# Power_Distribution_-_Load_Switchs_and_Co.net
KiCad netlist of a schematic drawn in Altium Designer
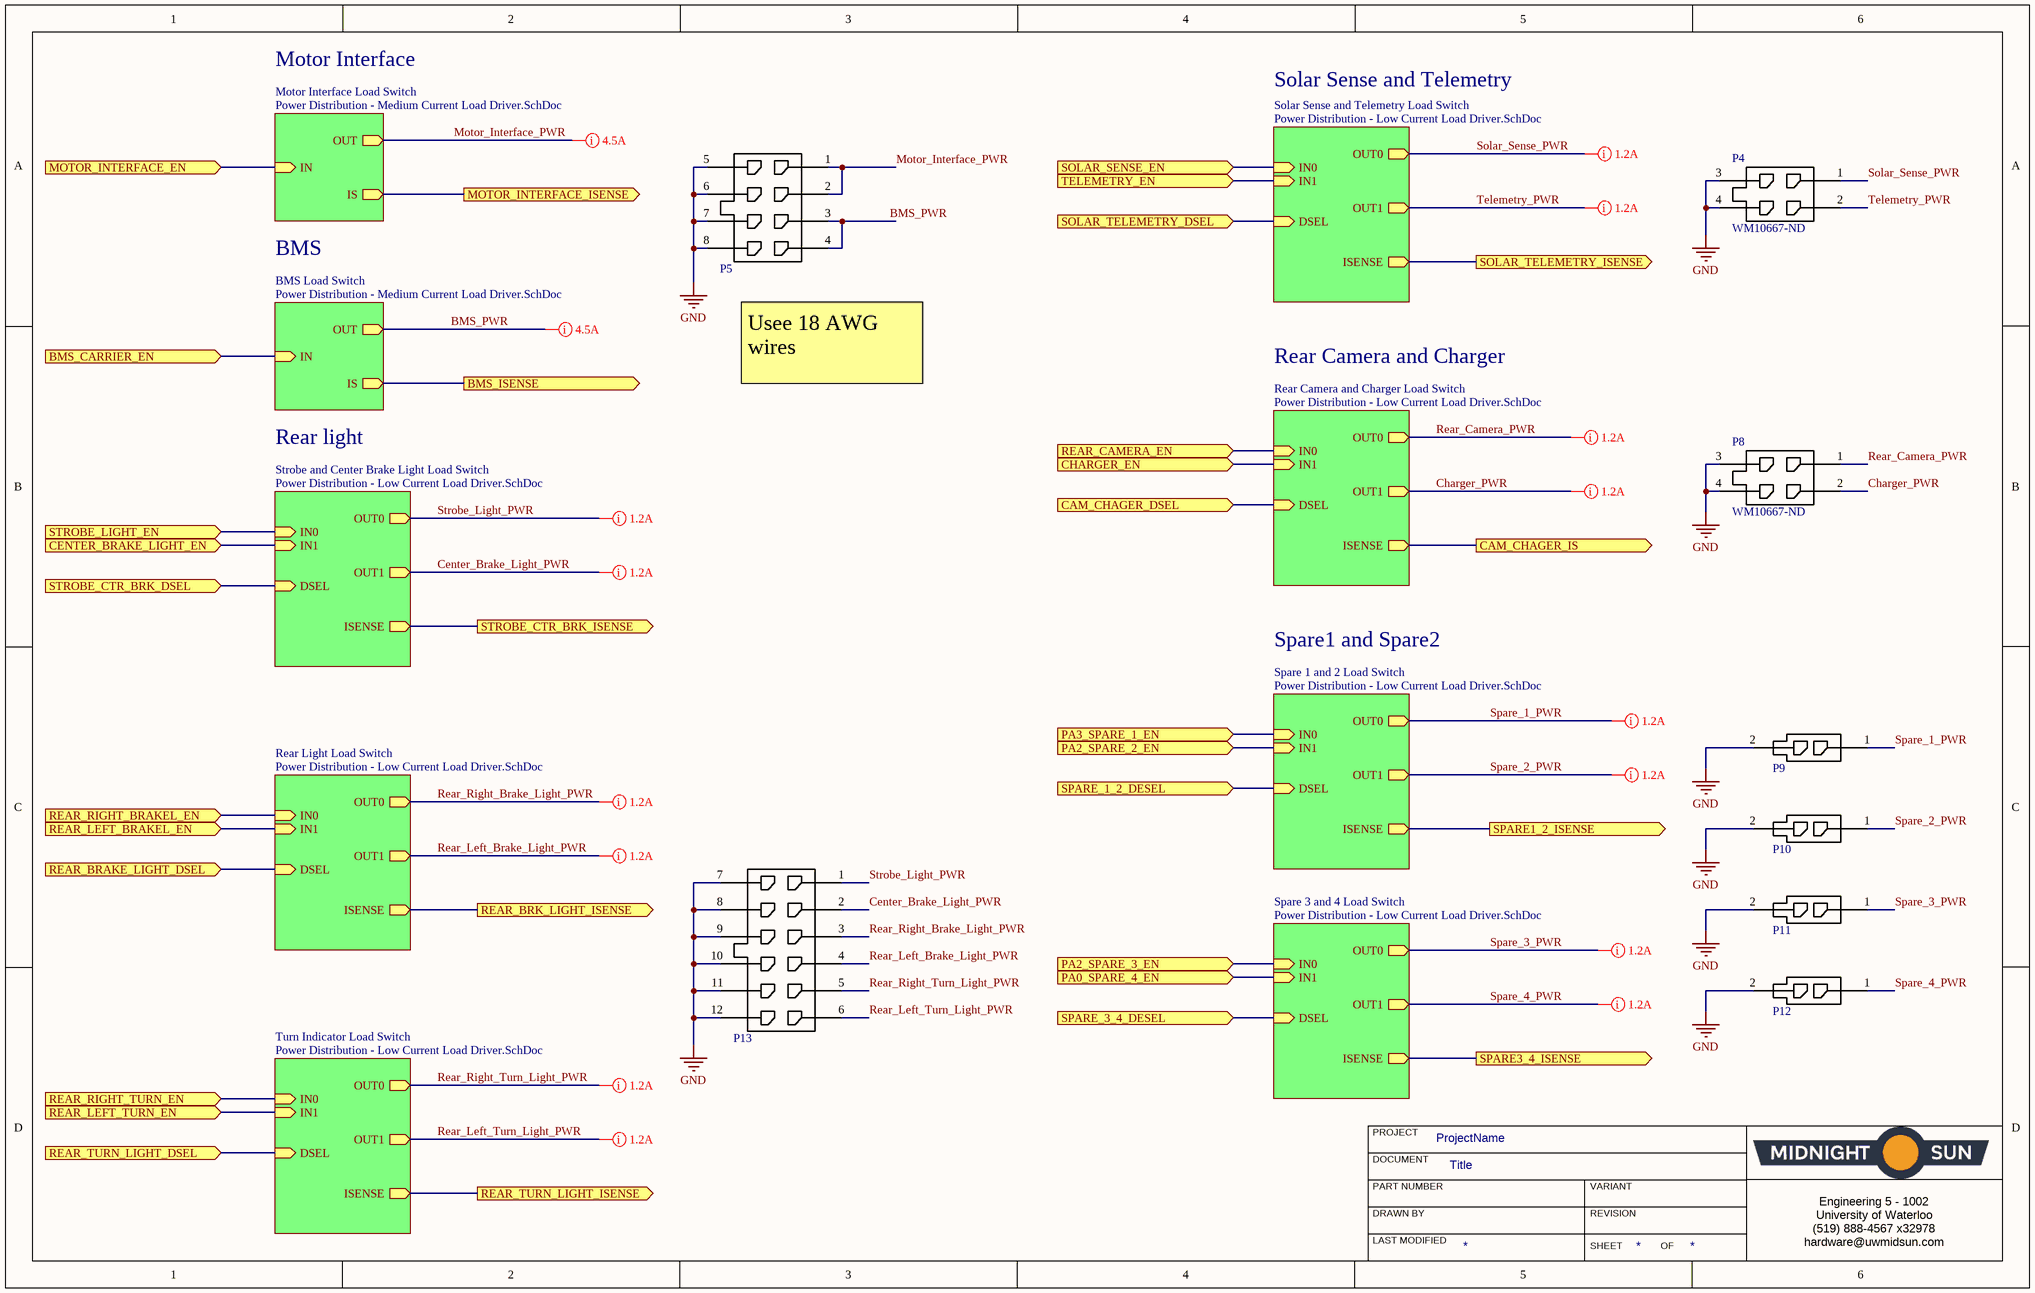
[diagram p0: Power Distribution - Load Switchs and Connectos.SchDoc]

(export (version "E")
  (design (tool "Eeschema 10.0.6"))
  (components
    (comp (ref "P4")
      (value "CONN 4POS MICRO-FIT 3mm")
      (footprint "CONN 4POS MICROFIT (2x2)")
      (fields
        (field (name "MANUFACTURER") "Molex, LLC")
        (field (name "MANUFACTURER PART NUMBER") "430450427")
        (field (name "SUPPLIER PART NUMBER 1") "WM10667-ND")
      )
      (libsource (lib "Schematic Diagrams") (part "CONN 4POS MICRO-FIT 3mm"))
    )
    (comp (ref "P5")
      (value "CONN 8POS MICRO-FIT 3mm")
      (footprint "CONN, 8POS MICRO-FIT")
      (description "Connector Header Through Hole 6 position 0.118\" (3.00mm)")
      (fields
        (field (name "MANUFACTURER") "Molex, LLC")
        (field (name "MANUFACTURER PART NUMBER") "0430450827")
      )
      (libsource (lib "Schematic Diagrams") (part "CONN 8POS MICRO-FIT 3mm"))
    )
    (comp (ref "P8")
      (value "CONN 4POS MICRO-FIT 3mm")
      (footprint "CONN 4POS MICROFIT (2x2)")
      (fields
        (field (name "MANUFACTURER") "Molex, LLC")
        (field (name "MANUFACTURER PART NUMBER") "430450427")
        (field (name "SUPPLIER PART NUMBER 1") "WM10667-ND")
      )
      (libsource (lib "Schematic Diagrams") (part "CONN 4POS MICRO-FIT 3mm"))
    )
    (comp (ref "P9")
      (value "CONN 2POS MICRO-FIT 3mm")
      (footprint "CONN, 2POS MICRO-FIT")
      (description "Connector Header Through Hole 2 position")
      (fields (field (name "MANUFACTURER") "Molex") (field (name "MANUFACTURER PART NUMBER") "43045-0227"))
      (libsource (lib "Schematic Diagrams") (part "CONN 2POS MICRO-FIT 3mm"))
    )
    (comp (ref "P10")
      (value "CONN 2POS MICRO-FIT 3mm")
      (footprint "CONN, 2POS MICRO-FIT")
      (description "Connector Header Through Hole 2 position")
      (fields (field (name "MANUFACTURER") "Molex") (field (name "MANUFACTURER PART NUMBER") "43045-0227"))
      (libsource (lib "Schematic Diagrams") (part "CONN 2POS MICRO-FIT 3mm"))
    )
    (comp (ref "P11")
      (value "CONN 2POS MICRO-FIT 3mm")
      (footprint "CONN, 2POS MICRO-FIT")
      (description "Connector Header Through Hole 2 position")
      (fields (field (name "MANUFACTURER") "Molex") (field (name "MANUFACTURER PART NUMBER") "43045-0227"))
      (libsource (lib "Schematic Diagrams") (part "CONN 2POS MICRO-FIT 3mm"))
    )
    (comp (ref "P12")
      (value "CONN 2POS MICRO-FIT 3mm")
      (footprint "CONN, 2POS MICRO-FIT")
      (description "Connector Header Through Hole 2 position")
      (fields (field (name "MANUFACTURER") "Molex") (field (name "MANUFACTURER PART NUMBER") "43045-0227"))
      (libsource (lib "Schematic Diagrams") (part "CONN 2POS MICRO-FIT 3mm"))
    )
    (comp (ref "P13")
      (value "CONN 12POS MICRO-FIT 3mm")
      (footprint "CONN, 12POS MICRO-FIT 3mm")
      (description "Connector Header Through Hole 12 position 0.118\" (3.00mm)")
      (fields
        (field (name "MANUFACTURER") "Molex, LLC")
        (field (name "MANUFACTURER PART NUMBER") "0430451227")
      )
      (libsource (lib "Schematic Diagrams") (part "CONN 12POS MICRO-FIT 3mm"))
    )
  )
  (nets
    (net (code "3") (name "/BMS_PWR") (class "Default")
      (node (ref "P5") (pin "3") (pinfunction "3_3") (pintype "passive"))
      (node (ref "P5") (pin "4") (pinfunction "4_4") (pintype "passive"))
    )
    (net (code "8") (name "/Center_Brake_Light_PWR") (class "Default")
      (node (ref "P13") (pin "2") (pinfunction "2_2") (pintype "passive"))
    )
    (net (code "9") (name "/Charger_PWR") (class "Default")
      (node (ref "P8") (pin "2") (pinfunction "2_2") (pintype "passive"))
    )
    (net (code "12") (name "/Motor_Interface_PWR") (class "Default")
      (node (ref "P5") (pin "1") (pinfunction "1_1") (pintype "passive"))
      (node (ref "P5") (pin "2") (pinfunction "2_2") (pintype "passive"))
    )
    (net (code "26") (name "/Rear_Camera_PWR") (class "Default")
      (node (ref "P8") (pin "1") (pinfunction "1_1") (pintype "passive"))
    )
    (net (code "27") (name "/Rear_Left_Brake_Light_PWR") (class "Default")
      (node (ref "P13") (pin "4") (pinfunction "4_4") (pintype "passive"))
    )
    (net (code "28") (name "/Rear_Left_Turn_Light_PWR") (class "Default")
      (node (ref "P13") (pin "6") (pinfunction "6_6") (pintype "passive"))
    )
    (net (code "29") (name "/Rear_Right_Brake_Light_PWR") (class "Default")
      (node (ref "P13") (pin "3") (pinfunction "3_3") (pintype "passive"))
    )
    (net (code "30") (name "/Rear_Right_Turn_Light_PWR") (class "Default")
      (node (ref "P13") (pin "5") (pinfunction "5_5") (pintype "passive"))
    )
    (net (code "41") (name "/Solar_Sense_PWR") (class "Default")
      (node (ref "P4") (pin "1") (pinfunction "1_1") (pintype "passive"))
    )
    (net (code "42") (name "/Spare_1_PWR") (class "Default")
      (node (ref "P9") (pin "1") (pinfunction "1_1") (pintype "passive"))
    )
    (net (code "43") (name "/Spare_2_PWR") (class "Default")
      (node (ref "P10") (pin "1") (pinfunction "1_1") (pintype "passive"))
    )
    (net (code "44") (name "/Spare_3_PWR") (class "Default")
      (node (ref "P11") (pin "1") (pinfunction "1_1") (pintype "passive"))
    )
    (net (code "45") (name "/Spare_4_PWR") (class "Default")
      (node (ref "P12") (pin "1") (pinfunction "1_1") (pintype "passive"))
    )
    (net (code "46") (name "/Strobe_Light_PWR") (class "Default")
      (node (ref "P13") (pin "1") (pinfunction "1_1") (pintype "passive"))
    )
    (net (code "48") (name "/Telemetry_PWR") (class "Default")
      (node (ref "P4") (pin "2") (pinfunction "2_2") (pintype "passive"))
    )
    (net (code "49") (name "GND") (class "Default")
      (node (ref "P10") (pin "2") (pinfunction "2_2") (pintype "passive"))
      (node (ref "P11") (pin "2") (pinfunction "2_2") (pintype "passive"))
      (node (ref "P12") (pin "2") (pinfunction "2_2") (pintype "passive"))
      (node (ref "P13") (pin "10") (pinfunction "10_10") (pintype "passive"))
      (node (ref "P13") (pin "11") (pinfunction "11_11") (pintype "passive"))
      (node (ref "P13") (pin "12") (pinfunction "12_12") (pintype "passive"))
      (node (ref "P13") (pin "7") (pinfunction "7_7") (pintype "passive"))
      (node (ref "P13") (pin "8") (pinfunction "8_8") (pintype "passive"))
      (node (ref "P13") (pin "9") (pinfunction "9_9") (pintype "passive"))
      (node (ref "P4") (pin "3") (pinfunction "3_3") (pintype "passive"))
      (node (ref "P4") (pin "4") (pinfunction "4_4") (pintype "passive"))
      (node (ref "P5") (pin "5") (pinfunction "5_5") (pintype "passive"))
      (node (ref "P5") (pin "6") (pinfunction "6_6") (pintype "passive"))
      (node (ref "P5") (pin "7") (pinfunction "7_7") (pintype "passive"))
      (node (ref "P5") (pin "8") (pinfunction "8_8") (pintype "passive"))
      (node (ref "P8") (pin "3") (pinfunction "3_3") (pintype "passive"))
      (node (ref "P8") (pin "4") (pinfunction "4_4") (pintype "passive"))
      (node (ref "P9") (pin "2") (pinfunction "2_2") (pintype "passive"))
    )
  )
)
